# TUDSSL_condenar__Hardware_PCBs_Logger_Sc.net
KiCad netlist of a schematic drawn in Altium Designer
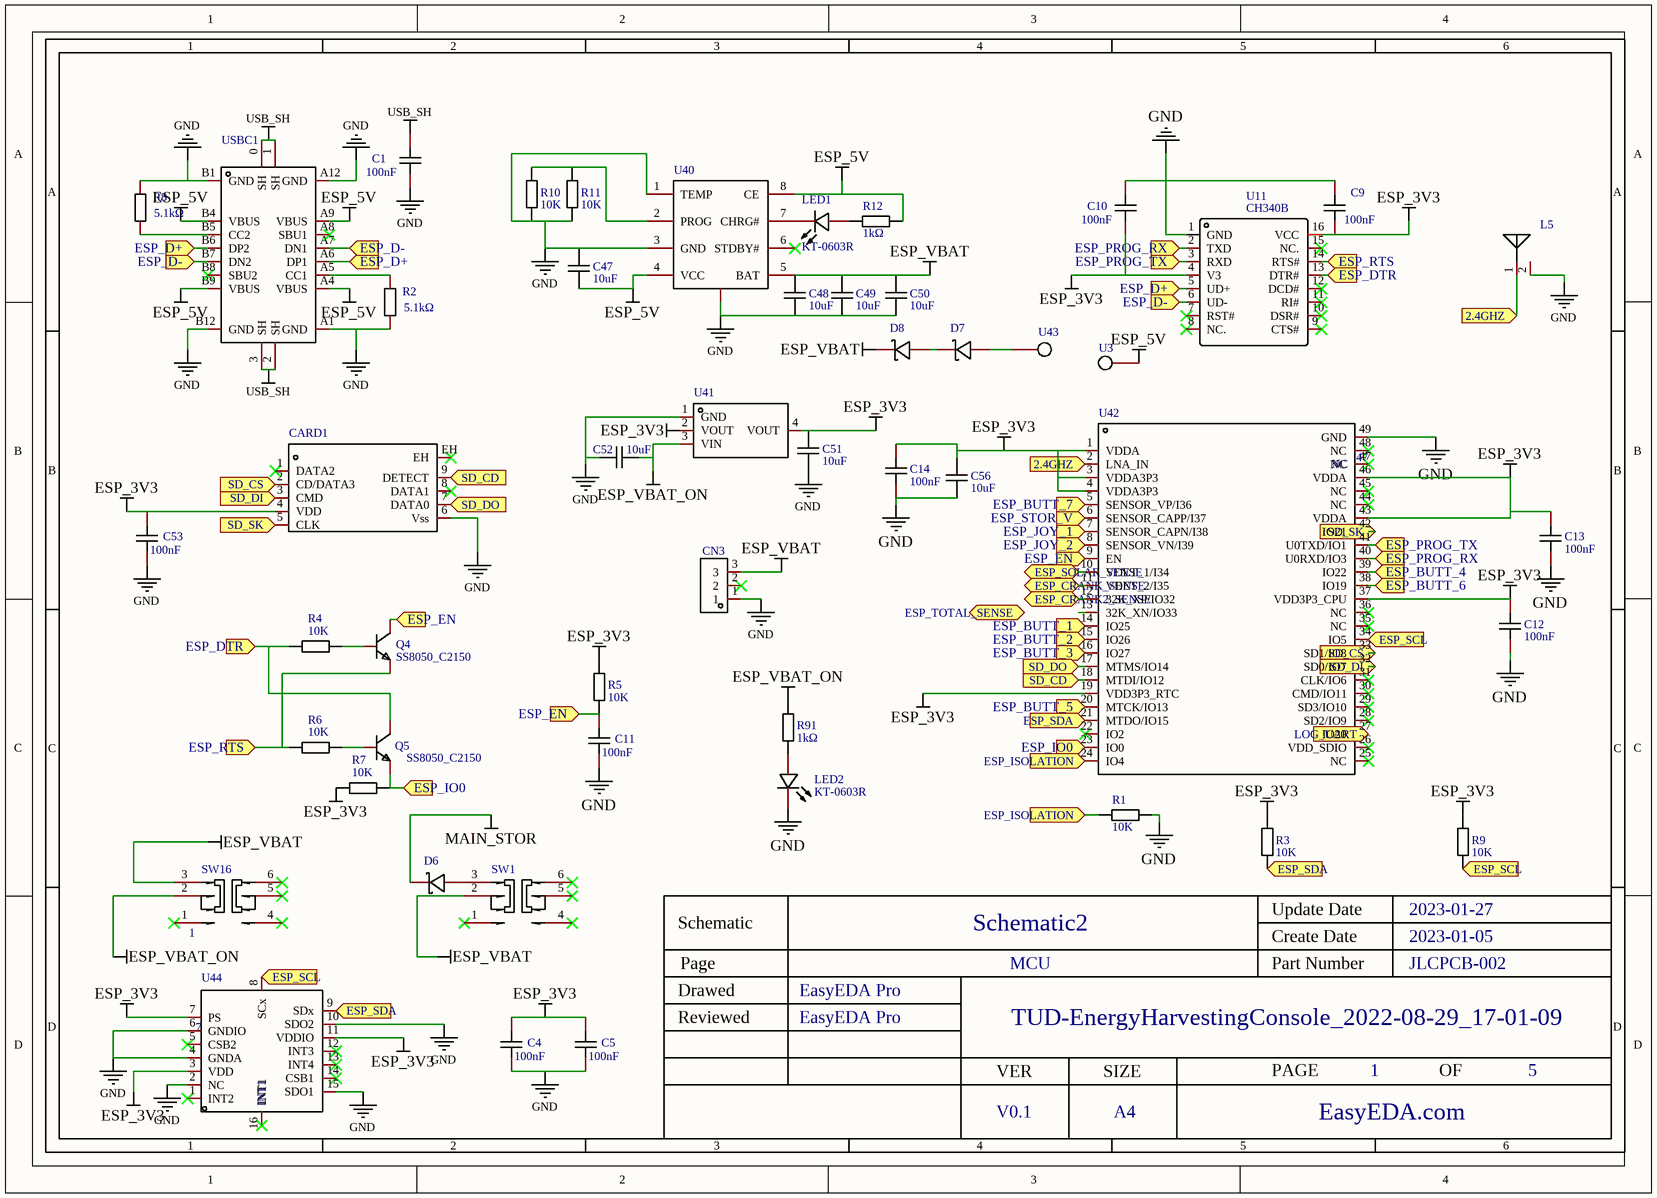
[diagram p0: TUDSSL_condenar__Hardware_PCBs_Logger_Schematic2__3_MCU.schdoc]

(export (version "E")
  (design (tool "Eeschema 10.0.6"))
  (components
    (comp (ref "C1")
      (value "100nF")
      (fields
        (field (name "NAME") "100nF")
        (field (name "MANUFACTURER") "YAGEO")
        (field (name "MANUFACTURER PART") "CC0603KRX7R9BB104")
      )
      (libsource (lib "altium-import") (part "root_1_CC0603KRX7R9BB104_"))
    )
    (comp (ref "C4")
      (value "100nF")
      (fields
        (field (name "NAME") "100nF")
        (field (name "MANUFACTURER") "YAGEO")
        (field (name "MANUFACTURER PART") "CC0603KRX7R9BB104")
      )
      (libsource (lib "altium-import") (part "root_1_CC0603KRX7R9BB104_"))
    )
    (comp (ref "C5")
      (value "100nF")
      (fields
        (field (name "NAME") "100nF")
        (field (name "MANUFACTURER") "YAGEO")
        (field (name "MANUFACTURER PART") "CC0603KRX7R9BB104")
      )
      (libsource (lib "altium-import") (part "root_1_CC0603KRX7R9BB104_"))
    )
    (comp (ref "C9")
      (value "100nF")
      (fields
        (field (name "NAME") "100nF")
        (field (name "MANUFACTURER") "YAGEO")
        (field (name "MANUFACTURER PART") "CC0603KRX7R9BB104")
      )
      (libsource (lib "altium-import") (part "root_1_CC0603KRX7R9BB104_"))
    )
    (comp (ref "C10")
      (value "100nF")
      (fields
        (field (name "NAME") "100nF")
        (field (name "MANUFACTURER") "YAGEO")
        (field (name "MANUFACTURER PART") "CC0603KRX7R9BB104")
      )
      (libsource (lib "altium-import") (part "root_1_CC0603KRX7R9BB104_"))
    )
    (comp (ref "C11")
      (value "100nF")
      (fields
        (field (name "NAME") "100nF")
        (field (name "MANUFACTURER") "YAGEO")
        (field (name "MANUFACTURER PART") "CC0603KRX7R9BB104")
      )
      (libsource (lib "altium-import") (part "root_1_CC0603KRX7R9BB104_"))
    )
    (comp (ref "C12")
      (value "100nF")
      (fields
        (field (name "NAME") "100nF")
        (field (name "MANUFACTURER PART") "CL05B104KO5NNNC")
        (field (name "MANUFACTURER") "SAMSUNG")
      )
      (libsource (lib "altium-import") (part "root_1_CL05B104KO5NNNC_"))
    )
    (comp (ref "C13")
      (value "100nF")
      (fields
        (field (name "NAME") "100nF")
        (field (name "MANUFACTURER PART") "CL05B104KO5NNNC")
        (field (name "MANUFACTURER") "SAMSUNG")
      )
      (libsource (lib "altium-import") (part "root_1_CL05B104KO5NNNC_"))
    )
    (comp (ref "C14")
      (value "100nF")
      (fields
        (field (name "NAME") "100nF")
        (field (name "MANUFACTURER PART") "CL05B104KO5NNNC")
        (field (name "MANUFACTURER") "SAMSUNG")
      )
      (libsource (lib "altium-import") (part "root_1_CL05B104KO5NNNC_"))
    )
    (comp (ref "C47")
      (value "10uF")
      (fields
        (field (name "NAME") "10uF")
        (field (name "MANUFACTURER PART") "CL05A106MQ5NUNC")
        (field (name "MANUFACTURER") "SAMSUNG")
      )
      (libsource (lib "altium-import") (part "root_3_CL05A106MQ5NUNC_"))
    )
    (comp (ref "C48")
      (value "10uF")
      (fields
        (field (name "NAME") "10uF")
        (field (name "MANUFACTURER PART") "CL05A106MQ5NUNC")
        (field (name "MANUFACTURER") "SAMSUNG")
      )
      (libsource (lib "altium-import") (part "root_3_CL05A106MQ5NUNC_"))
    )
    (comp (ref "C49")
      (value "10uF")
      (fields
        (field (name "NAME") "10uF")
        (field (name "MANUFACTURER PART") "CL05A106MQ5NUNC")
        (field (name "MANUFACTURER") "SAMSUNG")
      )
      (libsource (lib "altium-import") (part "root_3_CL05A106MQ5NUNC_"))
    )
    (comp (ref "C50")
      (value "10uF")
      (fields
        (field (name "NAME") "10uF")
        (field (name "MANUFACTURER PART") "CL05A106MQ5NUNC")
        (field (name "MANUFACTURER") "SAMSUNG")
      )
      (libsource (lib "altium-import") (part "root_3_CL05A106MQ5NUNC_"))
    )
    (comp (ref "C51")
      (value "10uF")
      (fields
        (field (name "NAME") "10uF")
        (field (name "MANUFACTURER PART") "CL05A106MQ5NUNC")
        (field (name "MANUFACTURER") "SAMSUNG")
      )
      (libsource (lib "altium-import") (part "root_3_CL05A106MQ5NUNC_"))
    )
    (comp (ref "C52")
      (value "10uF")
      (fields
        (field (name "NAME") "10uF")
        (field (name "MANUFACTURER PART") "CL05A106MQ5NUNC")
        (field (name "MANUFACTURER") "SAMSUNG")
      )
      (libsource (lib "altium-import") (part "root_0_CL05A106MQ5NUNC_"))
    )
    (comp (ref "C53")
      (value "100nF")
      (fields
        (field (name "NAME") "100nF")
        (field (name "MANUFACTURER") "YAGEO")
        (field (name "MANUFACTURER PART") "CC0603KRX7R9BB104")
      )
      (libsource (lib "altium-import") (part "root_1_CC0603KRX7R9BB104_"))
    )
    (comp (ref "C56")
      (value "10uF")
      (fields
        (field (name "NAME") "10uF")
        (field (name "MANUFACTURER PART") "CL05A106MQ5NUNC")
        (field (name "MANUFACTURER") "SAMSUNG")
      )
      (libsource (lib "altium-import") (part "root_3_CL05A106MQ5NUNC_"))
    )
    (comp (ref "CARD1")
      (value "473521001")
      (fields (field (name "MANUFACTURER") "MOLEX"))
      (libsource (lib "altium-import") (part "root_0_473521001_"))
    )
    (comp (ref "CN3")
      (value "X1502WR-03K-N0SN")
      (fields (field (name "MANUFACTURER") "XKB Connectivity(中国星坤)"))
      (libsource (lib "altium-import") (part "root_2_X1502WR-03K-N0SN_"))
    )
    (comp (ref "D6")
      (value "SS54")
      (description "Reverse Voltage (Vr):40V Average Rectified Current (Io):5A Forward Voltage (Vf@If):550mV@5A")
      (fields (field (name "MANUFACTURER") "MDD"))
      (libsource (lib "altium-import") (part "root_0_SS54_"))
    )
    (comp (ref "D7")
      (value "SS54")
      (description "Reverse Voltage (Vr):40V Average Rectified Current (Io):5A Forward Voltage (Vf@If):550mV@5A")
      (fields (field (name "MANUFACTURER") "MDD"))
      (libsource (lib "altium-import") (part "root_0_SS54_"))
    )
    (comp (ref "D8")
      (value "SS54")
      (description "Reverse Voltage (Vr):40V Average Rectified Current (Io):5A Forward Voltage (Vf@If):550mV@5A")
      (fields (field (name "MANUFACTURER") "MDD"))
      (libsource (lib "altium-import") (part "root_0_SS54_"))
    )
    (comp (ref "L5")
      (value "SLDA92-2R660G-S1TF")
      (fields (field (name "MANUFACTURER") "Sunlord(顺络)"))
      (libsource (lib "altium-import") (part "root_0_SLDA92-2R660G-S1TF_"))
    )
    (comp (ref "LED1")
      (value "KT-0603R")
      (fields (field (name "NAME") "KT-0603R") (field (name "MANUFACTURER") "KENTO"))
      (libsource (lib "altium-import") (part "root_0_KT-0603R_"))
    )
    (comp (ref "LED2")
      (value "KT-0603R")
      (fields (field (name "NAME") "KT-0603R") (field (name "MANUFACTURER") "KENTO"))
      (libsource (lib "altium-import") (part "root_1_KT-0603R_"))
    )
    (comp (ref "Q4")
      (value "SS8050_C2150")
      (fields
        (field (name "NAME") "SS8050_C2150")
        (field (name "MANUFACTURER") "CJ")
        (field (name "MANUFACTURER PART") "SS8050")
      )
      (libsource (lib "altium-import") (part "root_0_SS8050_"))
    )
    (comp (ref "Q5")
      (value "SS8050_C2150")
      (fields
        (field (name "NAME") "SS8050_C2150")
        (field (name "MANUFACTURER") "CJ")
        (field (name "MANUFACTURER PART") "SS8050")
      )
      (libsource (lib "altium-import") (part "root_0_SS8050_"))
    )
    (comp (ref "R1")
      (value "10K")
      (fields
        (field (name "NAME") "10K")
        (field (name "MANUFACTURER") "UniOhm")
        (field (name "MANUFACTURER PART") "0603WAF1002T5E")
      )
      (libsource (lib "altium-import") (part "root_2_0603WAF1002T5E_"))
    )
    (comp (ref "R2")
      (value "5.1kΩ")
      (fields
        (field (name "MANUFACTURER") "UNI-ROYAL(厚声)")
        (field (name "MANUFACTURER PART") "0603WAF5101T5E")
        (field (name "TOLERANCE") "±1%")
      )
      (libsource (lib "altium-import") (part "root_1_0603WAF5101T5E_"))
    )
    (comp (ref "R3")
      (value "10K")
      (fields
        (field (name "NAME") "10K")
        (field (name "MANUFACTURER") "UniOhm")
        (field (name "MANUFACTURER PART") "0603WAF1002T5E")
      )
      (libsource (lib "altium-import") (part "root_1_0603WAF1002T5E_"))
    )
    (comp (ref "R4")
      (value "10K")
      (fields
        (field (name "NAME") "10K")
        (field (name "MANUFACTURER") "UniOhm")
        (field (name "MANUFACTURER PART") "0603WAF1002T5E")
      )
      (libsource (lib "altium-import") (part "root_0_0603WAF1002T5E_"))
    )
    (comp (ref "R5")
      (value "10K")
      (fields
        (field (name "NAME") "10K")
        (field (name "MANUFACTURER") "UniOhm")
        (field (name "MANUFACTURER PART") "0603WAF1002T5E")
      )
      (libsource (lib "altium-import") (part "root_1_0603WAF1002T5E_"))
    )
    (comp (ref "R6")
      (value "10K")
      (fields
        (field (name "NAME") "10K")
        (field (name "MANUFACTURER") "UniOhm")
        (field (name "MANUFACTURER PART") "0603WAF1002T5E")
      )
      (libsource (lib "altium-import") (part "root_0_0603WAF1002T5E_"))
    )
    (comp (ref "R7")
      (value "10K")
      (fields
        (field (name "NAME") "10K")
        (field (name "MANUFACTURER") "UniOhm")
        (field (name "MANUFACTURER PART") "0603WAF1002T5E")
      )
      (libsource (lib "altium-import") (part "root_2_0603WAF1002T5E_"))
    )
    (comp (ref "R8")
      (value "5.1kΩ")
      (fields
        (field (name "MANUFACTURER") "UNI-ROYAL(厚声)")
        (field (name "MANUFACTURER PART") "0603WAF5101T5E")
        (field (name "TOLERANCE") "±1%")
      )
      (libsource (lib "altium-import") (part "root_1_0603WAF5101T5E_"))
    )
    (comp (ref "R9")
      (value "10K")
      (fields
        (field (name "NAME") "10K")
        (field (name "MANUFACTURER") "UniOhm")
        (field (name "MANUFACTURER PART") "0603WAF1002T5E")
      )
      (libsource (lib "altium-import") (part "root_1_0603WAF1002T5E_"))
    )
    (comp (ref "R10")
      (value "10K")
      (fields
        (field (name "NAME") "10K")
        (field (name "MANUFACTURER") "UniOhm")
        (field (name "MANUFACTURER PART") "0603WAF1002T5E")
      )
      (libsource (lib "altium-import") (part "root_1_0603WAF1002T5E_"))
    )
    (comp (ref "R11")
      (value "10K")
      (fields
        (field (name "NAME") "10K")
        (field (name "MANUFACTURER") "UniOhm")
        (field (name "MANUFACTURER PART") "0603WAF1002T5E")
      )
      (libsource (lib "altium-import") (part "root_1_0603WAF1002T5E_"))
    )
    (comp (ref "R12")
      (value "1kΩ")
      (fields
        (field (name "NAME") "1kΩ")
        (field (name "MANUFACTURER") "UniOhm")
        (field (name "MANUFACTURER PART") "0603WAF1001T5E")
      )
      (libsource (lib "altium-import") (part "root_0_0603WAF1001T5E_"))
    )
    (comp (ref "R91")
      (value "1kΩ")
      (fields
        (field (name "NAME") "1kΩ")
        (field (name "MANUFACTURER") "UniOhm")
        (field (name "MANUFACTURER PART") "0603WAF1001T5E")
      )
      (libsource (lib "altium-import") (part "root_1_0603WAF1001T5E_"))
    )
    (comp (ref "SW1")
      (value "SS-3235S-L1")
      (fields (field (name "MANUFACTURER") "XKB Connectivity(中国星坤)"))
      (libsource (lib "altium-import") (part "root_1_SS-3235S-L1_"))
    )
    (comp (ref "SW16")
      (value "SS-3235S-L1")
      (fields (field (name "MANUFACTURER") "XKB Connectivity(中国星坤)") (field (name "NUMBER") "1"))
      (libsource (lib "altium-import") (part "root_1_SS-3235S-L1_"))
    )
    (comp (ref "U3") (value "SMD_PAD") (libsource (lib "altium-import") (part "root_2_SMD_PAD_")))
    (comp (ref "U11")
      (value "CH340B")
      (fields (field (name "NAME") "CH340B") (field (name "MANUFACTURER") "WCH"))
      (libsource (lib "altium-import") (part "root_0_CH340B_"))
    )
    (comp (ref "U40")
      (value "TP4056M")
      (fields (field (name "MANUFACTURER") "TOPPOWER(南京拓微)"))
      (libsource (lib "altium-import") (part "root_0_TP4056M_"))
    )
    (comp (ref "U41")
      (value "AMS1117-3.3")
      (fields (field (name "MANUFACTURER") "美国AMS"))
      (libsource (lib "altium-import") (part "root_0_AMS1117-3.3_"))
    )
    (comp (ref "U42")
      (value "ESP32-PICO-V3")
      (fields
        (field (name "MANUFACTURER") "ESPRESSIF(乐鑫)")
        (field (name "NAME") "NC")
        (field (name "NUMBER") "47")
      )
      (libsource (lib "altium-import") (part "root_0_ESP32-PICO-V3_"))
    )
    (comp (ref "U43") (value "SMD_PAD") (libsource (lib "altium-import") (part "root_0_SMD_PAD_")))
    (comp (ref "U44")
      (value "BMI055")
      (fields
        (field (name "MANUFACTURER") "Bosch(博世)")
        (field (name "NAME") "INT1")
        (field (name "NUMBER") "7")
      )
      (libsource (lib "altium-import") (part "root_1_BMI055_"))
    )
    (comp (ref "USBC1")
      (value "TYPE-C-31-M-12")
      (fields (field (name "MANUFACTURER") "韩国韩荣"))
      (libsource (lib "altium-import") (part "root_0_TYPE-C-31-M-12_"))
    )
  )
  (nets
    (net (code "1") (name "/2.4GHZ") (class "Default")
      (node (ref "L5") (pin "1") (pinfunction "1_1") (pintype "passive"))
      (node (ref "U42") (pin "2") (pinfunction "LNA_IN_2") (pintype "passive"))
    )
    (net (code "2") (name "/ESP_BUTT_1") (class "Default")
      (node (ref "U42") (pin "14") (pinfunction "IO25_14") (pintype "passive"))
    )
    (net (code "3") (name "/ESP_BUTT_2") (class "Default")
      (node (ref "U42") (pin "15") (pinfunction "IO26_15") (pintype "passive"))
    )
    (net (code "4") (name "/ESP_BUTT_3") (class "Default")
      (node (ref "U42") (pin "16") (pinfunction "IO27_16") (pintype "passive"))
    )
    (net (code "5") (name "/ESP_BUTT_4") (class "Default")
      (node (ref "U42") (pin "39") (pinfunction "IO22_39") (pintype "passive"))
    )
    (net (code "6") (name "/ESP_BUTT_5") (class "Default")
      (node (ref "U42") (pin "20") (pinfunction "MTCK/IO13_20") (pintype "passive"))
    )
    (net (code "7") (name "/ESP_BUTT_6") (class "Default")
      (node (ref "U42") (pin "38") (pinfunction "IO19_38") (pintype "passive"))
    )
    (net (code "8") (name "/ESP_BUTT_7") (class "Default")
      (node (ref "U42") (pin "5") (pinfunction "SENSOR_VP/I36_5") (pintype "passive"))
    )
    (net (code "9") (name "/ESP_CRANK2_SENSE") (class "Default")
      (node (ref "U42") (pin "12") (pinfunction "32K_XP/IO32_12") (pintype "passive"))
    )
    (net (code "10") (name "/ESP_CRANK_SENSE") (class "Default")
      (node (ref "U42") (pin "11") (pinfunction "VDET_2/I35_11") (pintype "passive"))
    )
    (net (code "11") (name "/ESP_D+") (class "Default")
      (node (ref "U11") (pin "5") (pinfunction "UD+_5") (pintype "passive"))
      (node (ref "USBC1") (pin "A6") (pinfunction "DP1_A6") (pintype "passive"))
      (node (ref "USBC1") (pin "B6") (pinfunction "DP2_B6") (pintype "passive"))
    )
    (net (code "12") (name "/ESP_D-") (class "Default")
      (node (ref "U11") (pin "6") (pinfunction "UD-_6") (pintype "passive"))
      (node (ref "USBC1") (pin "A7") (pinfunction "DN1_A7") (pintype "passive"))
      (node (ref "USBC1") (pin "B7") (pinfunction "DN2_B7") (pintype "passive"))
    )
    (net (code "13") (name "/ESP_DTR") (class "Default")
      (node (ref "Q5") (pin "3") (pinfunction "C_3") (pintype "passive"))
      (node (ref "R4") (pin "1") (pinfunction "1_1") (pintype "passive"))
      (node (ref "U11") (pin "13") (pinfunction "DTR#_13") (pintype "passive"))
    )
    (net (code "14") (name "/ESP_EN") (class "Default")
      (node (ref "C11") (pin "2") (pinfunction "2_2") (pintype "passive"))
      (node (ref "Q4") (pin "3") (pinfunction "C_3") (pintype "passive"))
      (node (ref "R5") (pin "1") (pinfunction "1_1") (pintype "passive"))
      (node (ref "U42") (pin "9") (pinfunction "EN_9") (pintype "passive"))
    )
    (net (code "15") (name "/ESP_IO0") (class "Default")
      (node (ref "Q5") (pin "2") (pinfunction "E_2") (pintype "passive"))
      (node (ref "R7") (pin "1") (pinfunction "1_1") (pintype "passive"))
      (node (ref "U42") (pin "23") (pinfunction "IO0_23") (pintype "passive"))
    )
    (net (code "16") (name "/ESP_ISOLATION") (class "Default")
      (node (ref "R1") (pin "2") (pinfunction "2_2") (pintype "passive"))
      (node (ref "U42") (pin "24") (pinfunction "IO4_24") (pintype "passive"))
    )
    (net (code "17") (name "/ESP_JOY_1") (class "Default")
      (node (ref "U42") (pin "7") (pinfunction "SENSOR_CAPN/I38_7") (pintype "passive"))
    )
    (net (code "18") (name "/ESP_JOY_2") (class "Default")
      (node (ref "U42") (pin "8") (pinfunction "SENSOR_VN/I39_8") (pintype "passive"))
    )
    (net (code "19") (name "/ESP_PROG_RX") (class "Default")
      (node (ref "U11") (pin "2") (pinfunction "TXD_2") (pintype "passive"))
      (node (ref "U42") (pin "40") (pinfunction "U0RXD/IO3_40") (pintype "passive"))
    )
    (net (code "20") (name "/ESP_PROG_TX") (class "Default")
      (node (ref "U11") (pin "3") (pinfunction "RXD_3") (pintype "passive"))
      (node (ref "U42") (pin "41") (pinfunction "U0TXD/IO1_41") (pintype "passive"))
    )
    (net (code "21") (name "/ESP_RTS") (class "Default")
      (node (ref "Q4") (pin "2") (pinfunction "E_2") (pintype "passive"))
      (node (ref "R6") (pin "1") (pinfunction "1_1") (pintype "passive"))
      (node (ref "U11") (pin "14") (pinfunction "RTS#_14") (pintype "passive"))
    )
    (net (code "22") (name "/ESP_SCL") (class "Default")
      (node (ref "R9") (pin "1") (pinfunction "1_1") (pintype "passive"))
      (node (ref "U42") (pin "34") (pinfunction "IO5_34") (pintype "passive"))
      (node (ref "U44") (pin "8") (pinfunction "SCx_8") (pintype "passive"))
    )
    (net (code "23") (name "/ESP_SDA") (class "Default")
      (node (ref "R3") (pin "1") (pinfunction "1_1") (pintype "passive"))
      (node (ref "U42") (pin "21") (pinfunction "MTDO/IO15_21") (pintype "passive"))
      (node (ref "U44") (pin "9") (pinfunction "SDx_9") (pintype "passive"))
    )
    (net (code "24") (name "/ESP_SOLAR_SENSE") (class "Default")
      (node (ref "U42") (pin "10") (pinfunction "VDET_1/I34_10") (pintype "passive"))
    )
    (net (code "25") (name "/ESP_STOR_V") (class "Default")
      (node (ref "U42") (pin "6") (pinfunction "SENSOR_CAPP/I37_6") (pintype "passive"))
    )
    (net (code "27") (name "/LOG_UART") (class "Default")
      (node (ref "U42") (pin "27") (pinfunction "IO20_27") (pintype "passive"))
    )
    (net (code "28") (name "/SD_CD") (class "Default")
      (node (ref "CARD1") (pin "9") (pinfunction "DETECT_9") (pintype "passive"))
      (node (ref "U42") (pin "18") (pinfunction "MTDI/IO12_18") (pintype "passive"))
    )
    (net (code "29") (name "/SD_CS") (class "Default")
      (node (ref "CARD1") (pin "2") (pinfunction "CD/DATA3_2") (pintype "passive"))
      (node (ref "U42") (pin "33") (pinfunction "SD1/IO8_33") (pintype "passive"))
    )
    (net (code "30") (name "/SD_DI") (class "Default")
      (node (ref "CARD1") (pin "3") (pinfunction "CMD_3") (pintype "passive"))
      (node (ref "U42") (pin "32") (pinfunction "SD0/IO7_32") (pintype "passive"))
    )
    (net (code "31") (name "/SD_DO") (class "Default")
      (node (ref "CARD1") (pin "7") (pinfunction "DATA0_7") (pintype "passive"))
      (node (ref "U42") (pin "17") (pinfunction "MTMS/IO14_17") (pintype "passive"))
    )
    (net (code "32") (name "/SD_SK") (class "Default")
      (node (ref "CARD1") (pin "5") (pinfunction "CLK_5") (pintype "passive"))
      (node (ref "U42") (pin "42") (pinfunction "IO21_42") (pintype "passive"))
    )
    (net (code "33") (name "ESP_3V3") (class "Default")
      (node (ref "C10") (pin "1") (pinfunction "1_1") (pintype "passive"))
      (node (ref "C12") (pin "2") (pinfunction "2_2") (pintype "passive"))
      (node (ref "C13") (pin "2") (pinfunction "2_2") (pintype "passive"))
      (node (ref "C14") (pin "2") (pinfunction "2_2") (pintype "passive"))
      (node (ref "C4") (pin "2") (pinfunction "2_2") (pintype "passive"))
      (node (ref "C5") (pin "2") (pinfunction "2_2") (pintype "passive"))
      (node (ref "C51") (pin "1") (pinfunction "1_1") (pintype "passive"))
      (node (ref "C53") (pin "2") (pinfunction "2_2") (pintype "passive"))
      (node (ref "C56") (pin "1") (pinfunction "1_1") (pintype "passive"))
      (node (ref "C9") (pin "1") (pinfunction "1_1") (pintype "passive"))
      (node (ref "CARD1") (pin "4") (pinfunction "VDD_4") (pintype "passive"))
      (node (ref "R3") (pin "2") (pinfunction "2_2") (pintype "passive"))
      (node (ref "R5") (pin "2") (pinfunction "2_2") (pintype "passive"))
      (node (ref "R7") (pin "2") (pinfunction "2_2") (pintype "passive"))
      (node (ref "R9") (pin "2") (pinfunction "2_2") (pintype "passive"))
      (node (ref "U11") (pin "16") (pinfunction "VCC_16") (pintype "passive"))
      (node (ref "U11") (pin "4") (pinfunction "V3_4") (pintype "passive"))
      (node (ref "U41") (pin "2") (pinfunction "VOUT_2") (pintype "passive"))
      (node (ref "U41") (pin "4") (pinfunction "VOUT_4") (pintype "passive"))
      (node (ref "U42") (pin "1") (pinfunction "VDDA_1") (pintype "passive"))
      (node (ref "U42") (pin "19") (pinfunction "VDD3P3_RTC_19") (pintype "passive"))
      (node (ref "U42") (pin "3") (pinfunction "VDDA3P3_3") (pintype "passive"))
      (node (ref "U42") (pin "37") (pinfunction "VDD3P3_CPU_37") (pintype "passive"))
      (node (ref "U42") (pin "4") (pinfunction "VDDA3P3_4") (pintype "passive"))
      (node (ref "U42") (pin "43") (pinfunction "VDDA_43") (pintype "passive"))
      (node (ref "U42") (pin "46") (pinfunction "VDDA_46") (pintype "passive"))
      (node (ref "U44") (pin "11") (pinfunction "VDDIO_11") (pintype "passive"))
      (node (ref "U44") (pin "3") (pinfunction "VDD_3") (pintype "passive"))
      (node (ref "U44") (pin "7") (pinfunction "PS_7") (pintype "passive"))
    )
    (net (code "34") (name "ESP_5V") (class "Default")
      (node (ref "C47") (pin "2") (pinfunction "2_2") (pintype "passive"))
      (node (ref "R12") (pin "2") (pinfunction "2_2") (pintype "passive"))
      (node (ref "U3") (pin "1") (pinfunction "1_1") (pintype "passive"))
      (node (ref "U40") (pin "4") (pinfunction "VCC_4") (pintype "passive"))
      (node (ref "U40") (pin "8") (pinfunction "CE_8") (pintype "passive"))
      (node (ref "USBC1") (pin "A4") (pinfunction "VBUS_A4") (pintype "passive"))
      (node (ref "USBC1") (pin "A9") (pinfunction "VBUS_A9") (pintype "passive"))
      (node (ref "USBC1") (pin "B4") (pinfunction "VBUS_B4") (pintype "passive"))
      (node (ref "USBC1") (pin "B9") (pinfunction "VBUS_B9") (pintype "passive"))
    )
    (net (code "35") (name "ESP_VBAT") (class "Default")
      (node (ref "C48") (pin "1") (pinfunction "1_1") (pintype "passive"))
      (node (ref "C49") (pin "1") (pinfunction "1_1") (pintype "passive"))
      (node (ref "C50") (pin "1") (pinfunction "1_1") (pintype "passive"))
      (node (ref "CN3") (pin "3") (pinfunction "3_3") (pintype "passive"))
      (node (ref "D8") (pin "2") (pinfunction "K_2") (pintype "passive"))
      (node (ref "SW1") (pin "2") (pinfunction "2_2") (pintype "passive"))
      (node (ref "SW16") (pin "3") (pinfunction "3_3") (pintype "passive"))
      (node (ref "U40") (pin "5") (pinfunction "BAT_5") (pintype "passive"))
    )
    (net (code "36") (name "ESP_VBAT_ON") (class "Default")
      (node (ref "C52") (pin "2") (pinfunction "2_2") (pintype "passive"))
      (node (ref "R91") (pin "2") (pinfunction "2_2") (pintype "passive"))
      (node (ref "SW16") (pin "2") (pinfunction "2_2") (pintype "passive"))
      (node (ref "U41") (pin "3") (pinfunction "VIN_3") (pintype "passive"))
    )
    (net (code "37") (name "GND") (class "Default")
      (node (ref "C1") (pin "1") (pinfunction "1_1") (pintype "passive"))
      (node (ref "C10") (pin "2") (pinfunction "2_2") (pintype "passive"))
      (node (ref "C11") (pin "1") (pinfunction "1_1") (pintype "passive"))
      (node (ref "C12") (pin "1") (pinfunction "1_1") (pintype "passive"))
      (node (ref "C13") (pin "1") (pinfunction "1_1") (pintype "passive"))
      (node (ref "C14") (pin "1") (pinfunction "1_1") (pintype "passive"))
      (node (ref "C4") (pin "1") (pinfunction "1_1") (pintype "passive"))
      (node (ref "C47") (pin "1") (pinfunction "1_1") (pintype "passive"))
      (node (ref "C48") (pin "2") (pinfunction "2_2") (pintype "passive"))
      (node (ref "C49") (pin "2") (pinfunction "2_2") (pintype "passive"))
      (node (ref "C5") (pin "1") (pinfunction "1_1") (pintype "passive"))
      (node (ref "C50") (pin "2") (pinfunction "2_2") (pintype "passive"))
      (node (ref "C51") (pin "2") (pinfunction "2_2") (pintype "passive"))
      (node (ref "C52") (pin "1") (pinfunction "1_1") (pintype "passive"))
      (node (ref "C53") (pin "1") (pinfunction "1_1") (pintype "passive"))
      (node (ref "C56") (pin "2") (pinfunction "2_2") (pintype "passive"))
      (node (ref "C9") (pin "2") (pinfunction "2_2") (pintype "passive"))
      (node (ref "CARD1") (pin "6") (pinfunction "Vss_6") (pintype "passive"))
      (node (ref "CN3") (pin "1") (pinfunction "1_1") (pintype "passive"))
      (node (ref "L5") (pin "2") (pinfunction "NC_2") (pintype "passive"))
      (node (ref "LED2") (pin "2") (pinfunction "K_2") (pintype "passive"))
      (node (ref "R1") (pin "1") (pinfunction "1_1") (pintype "passive"))
      (node (ref "R10") (pin "1") (pinfunction "1_1") (pintype "passive"))
      (node (ref "R11") (pin "1") (pinfunction "1_1") (pintype "passive"))
      (node (ref "R2") (pin "1") (pinfunction "1_1") (pintype "passive"))
      (node (ref "R8") (pin "2") (pinfunction "2_2") (pintype "passive"))
      (node (ref "U11") (pin "1") (pinfunction "GND_1") (pintype "passive"))
      (node (ref "U40") (pin "1") (pinfunction "TEMP_1") (pintype "passive"))
      (node (ref "U40") (pin "3") (pinfunction "GND_3") (pintype "passive"))
      (node (ref "U40") (pin "9") (pinfunction "9_9") (pintype "passive"))
      (node (ref "U41") (pin "1") (pinfunction "GND_1") (pintype "passive"))
      (node (ref "U42") (pin "49") (pinfunction "GND_49") (pintype "passive"))
      (node (ref "U44") (pin "10") (pinfunction "SDO2_10") (pintype "passive"))
      (node (ref "U44") (pin "15") (pinfunction "SDO1_15") (pintype "passive"))
      (node (ref "U44") (pin "2") (pinfunction "NC_2") (pintype "passive"))
      (node (ref "U44") (pin "4") (pinfunction "GNDA_4") (pintype "passive"))
      (node (ref "U44") (pin "6") (pinfunction "GNDIO_6") (pintype "passive"))
      (node (ref "USBC1") (pin "A1") (pinfunction "GND_A1") (pintype "passive"))
      (node (ref "USBC1") (pin "A12") (pinfunction "GND_A12") (pintype "passive"))
      (node (ref "USBC1") (pin "B1") (pinfunction "GND_B1") (pintype "passive"))
      (node (ref "USBC1") (pin "B12") (pinfunction "GND_B12") (pintype "passive"))
    )
    (net (code "38") (name "MAIN_STOR") (class "Default")
      (node (ref "D6") (pin "2") (pinfunction "K_2") (pintype "passive"))
    )
    (net (code "39") (name "Net-(D6-A)") (class "Default")
      (node (ref "D6") (pin "1") (pinfunction "A_1") (pintype "passive"))
      (node (ref "SW1") (pin "3") (pinfunction "3_3") (pintype "passive"))
    )
    (net (code "40") (name "Net-(D7-A)") (class "Default")
      (node (ref "D7") (pin "1") (pinfunction "A_1") (pintype "passive"))
      (node (ref "U43") (pin "1") (pinfunction "1_1") (pintype "passive"))
    )
    (net (code "41") (name "Net-(D7-K)") (class "Default")
      (node (ref "D7") (pin "2") (pinfunction "K_2") (pintype "passive"))
      (node (ref "D8") (pin "1") (pinfunction "A_1") (pintype "passive"))
    )
    (net (code "42") (name "Net-(LED1-A)") (class "Default")
      (node (ref "LED1") (pin "1") (pinfunction "A_1") (pintype "passive"))
      (node (ref "R12") (pin "1") (pinfunction "1_1") (pintype "passive"))
    )
    (net (code "43") (name "Net-(LED1-K)") (class "Default")
      (node (ref "LED1") (pin "2") (pinfunction "K_2") (pintype "passive"))
      (node (ref "U40") (pin "7") (pinfunction "CHRG#_7") (pintype "passive"))
    )
    (net (code "44") (name "Net-(LED2-A)") (class "Default")
      (node (ref "LED2") (pin "1") (pinfunction "A_1") (pintype "passive"))
      (node (ref "R91") (pin "1") (pinfunction "1_1") (pintype "passive"))
    )
    (net (code "45") (name "Net-(Q4-B)") (class "Default")
      (node (ref "Q4") (pin "1") (pinfunction "B_1") (pintype "passive"))
      (node (ref "R4") (pin "2") (pinfunction "2_2") (pintype "passive"))
    )
    (net (code "46") (name "Net-(Q5-B)") (class "Default")
      (node (ref "Q5") (pin "1") (pinfunction "B_1") (pintype "passive"))
      (node (ref "R6") (pin "2") (pinfunction "2_2") (pintype "passive"))
    )
    (net (code "47") (name "Net-(U40-PROG)") (class "Default")
      (node (ref "R10") (pin "2") (pinfunction "2_2") (pintype "passive"))
      (node (ref "R11") (pin "2") (pinfunction "2_2") (pintype "passive"))
      (node (ref "U40") (pin "2") (pinfunction "PROG_2") (pintype "passive"))
    )
    (net (code "48") (name "Net-(USBC1-CC1)") (class "Default")
      (node (ref "R2") (pin "2") (pinfunction "2_2") (pintype "passive"))
      (node (ref "USBC1") (pin "A5") (pinfunction "CC1_A5") (pintype "passive"))
    )
    (net (code "49") (name "Net-(USBC1-CC2)") (class "Default")
      (node (ref "R8") (pin "1") (pinfunction "1_1") (pintype "passive"))
      (node (ref "USBC1") (pin "B5") (pinfunction "CC2_B5") (pintype "passive"))
    )
    (net (code "50") (name "USB_SH") (class "Default")
      (node (ref "C1") (pin "2") (pinfunction "2_2") (pintype "passive"))
      (node (ref "USBC1") (pin "0") (pinfunction "SH_0") (pintype "passive"))
      (node (ref "USBC1") (pin "1") (pinfunction "SH_1") (pintype "passive"))
      (node (ref "USBC1") (pin "2") (pinfunction "SH_2") (pintype "passive"))
      (node (ref "USBC1") (pin "3") (pinfunction "SH_3") (pintype "passive"))
    )
    (net (code "51") (name "unconnected-(CARD1-DATA1-Pad8)") (class "Default")
      (node (ref "CARD1") (pin "8") (pinfunction "DATA1_8") (pintype "passive+no_connect"))
    )
    (net (code "52") (name "unconnected-(CARD1-DATA2-Pad1)") (class "Default")
      (node (ref "CARD1") (pin "1") (pinfunction "DATA2_1") (pintype "passive+no_connect"))
    )
    (net (code "53") (name "unconnected-(CARD1-PadEH)") (class "Default")
      (node (ref "CARD1") (pin "EH") (pinfunction "EH_EH") (pintype "passive+no_connect"))
    )
    (net (code "54") (name "unconnected-(CN3-Pad2)") (class "Default")
      (node (ref "CN3") (pin "2") (pinfunction "2_2") (pintype "passive+no_connect"))
    )
    (net (code "55") (name "unconnected-(SW1-Pad1)") (class "Default")
      (node (ref "SW1") (pin "1") (pinfunction "1_1") (pintype "passive+no_connect"))
    )
    (net (code "56") (name "unconnected-(SW1-Pad4)") (class "Default")
      (node (ref "SW1") (pin "4") (pinfunction "4_4") (pintype "passive+no_connect"))
    )
    (net (code "57") (name "unconnected-(SW1-Pad5)") (class "Default")
      (node (ref "SW1") (pin "5") (pinfunction "5_5") (pintype "passive+no_connect"))
    )
    (net (code "58") (name "unconnected-(SW1-Pad6)") (class "Default")
      (node (ref "SW1") (pin "6") (pinfunction "6_6") (pintype "passive+no_connect"))
    )
    (net (code "59") (name "unconnected-(SW16-Pad1)") (class "Default")
      (node (ref "SW16") (pin "1") (pinfunction "1_1") (pintype "passive+no_connect"))
    )
    (net (code "60") (name "unconnected-(SW16-Pad4)") (class "Default")
      (node (ref "SW16") (pin "4") (pinfunction "4_4") (pintype "passive+no_connect"))
    )
    (net (code "61") (name "unconnected-(SW16-Pad5)") (class "Default")
      (node (ref "SW16") (pin "5") (pinfunction "5_5") (pintype "passive+no_connect"))
    )
    (net (code "62") (name "unconnected-(SW16-Pad6)") (class "Default")
      (node (ref "SW16") (pin "6") (pinfunction "6_6") (pintype "passive+no_connect"))
    )
    (net (code "63") (name "unconnected-(U11-CTS#-Pad9)") (class "Default")
      (node (ref "U11") (pin "9") (pinfunction "CTS#_9") (pintype "passive+no_connect"))
    )
    (net (code "64") (name "unconnected-(U11-DCD#-Pad12)") (class "Default")
      (node (ref "U11") (pin "12") (pinfunction "DCD#_12") (pintype "passive+no_connect"))
    )
    (net (code "65") (name "unconnected-(U11-DSR#-Pad10)") (class "Default")
      (node (ref "U11") (pin "10") (pinfunction "DSR#_10") (pintype "passive+no_connect"))
    )
    (net (code "66") (name "unconnected-(U11-NC.-Pad8)") (class "Default")
      (node (ref "U11") (pin "8") (pinfunction "NC._8") (pintype "passive+no_connect"))
    )
    (net (code "67") (name "unconnected-(U11-NC.-Pad15)") (class "Default")
      (node (ref "U11") (pin "15") (pinfunction "NC._15") (pintype "passive+no_connect"))
    )
    (net (code "68") (name "unconnected-(U11-RI#-Pad11)") (class "Default")
      (node (ref "U11") (pin "11") (pinfunction "RI#_11") (pintype "passive+no_connect"))
    )
    (net (code "69") (name "unconnected-(U11-RST#-Pad7)") (class "Default")
      (node (ref "U11") (pin "7") (pinfunction "RST#_7") (pintype "passive+no_connect"))
    )
    (net (code "70") (name "unconnected-(U40-STDBY#-Pad6)") (class "Default")
      (node (ref "U40") (pin "6") (pinfunction "STDBY#_6") (pintype "passive+no_connect"))
    )
    (net (code "71") (name "unconnected-(U42-32K_XN{slash}IO33-Pad13)") (class "Default")
      (node (ref "U42") (pin "13") (pinfunction "32K_XN/IO33_13") (pintype "passive"))
    )
    (net (code "72") (name "unconnected-(U42-CLK{slash}IO6-Pad31)") (class "Default")
      (node (ref "U42") (pin "31") (pinfunction "CLK/IO6_31") (pintype "passive+no_connect"))
    )
    (net (code "73") (name "unconnected-(U42-CMD{slash}IO11-Pad30)") (class "Default")
      (node (ref "U42") (pin "30") (pinfunction "CMD/IO11_30") (pintype "passive+no_connect"))
    )
    (net (code "74") (name "unconnected-(U42-IO2-Pad22)") (class "Default")
      (node (ref "U42") (pin "22") (pinfunction "IO2_22") (pintype "passive+no_connect"))
    )
    (net (code "75") (name "unconnected-(U42-NC-Pad25)") (class "Default")
      (node (ref "U42") (pin "25") (pinfunction "NC_25") (pintype "passive+no_connect"))
    )
    (net (code "76") (name "unconnected-(U42-NC-Pad35)") (class "Default")
      (node (ref "U42") (pin "35") (pinfunction "NC_35") (pintype "passive+no_connect"))
    )
    (net (code "77") (name "unconnected-(U42-NC-Pad36)") (class "Default")
      (node (ref "U42") (pin "36") (pinfunction "NC_36") (pintype "passive+no_connect"))
    )
    (net (code "78") (name "unconnected-(U42-NC-Pad44)") (class "Default")
      (node (ref "U42") (pin "44") (pinfunction "NC_44") (pintype "passive+no_connect"))
    )
    (net (code "79") (name "unconnected-(U42-NC-Pad45)") (class "Default")
      (node (ref "U42") (pin "45") (pinfunction "NC_45") (pintype "passive+no_connect"))
    )
    (net (code "80") (name "unconnected-(U42-NC-Pad47)") (class "Default")
      (node (ref "U42") (pin "47") (pinfunction "NC_47") (pintype "passive+no_connect"))
    )
    (net (code "81") (name "unconnected-(U42-NC-Pad48)") (class "Default")
      (node (ref "U42") (pin "48") (pinfunction "NC_48") (pintype "passive+no_connect"))
    )
    (net (code "82") (name "unconnected-(U42-SD2{slash}IO9-Pad28)") (class "Default")
      (node (ref "U42") (pin "28") (pinfunction "SD2/IO9_28") (pintype "passive+no_connect"))
    )
    (net (code "83") (name "unconnected-(U42-SD3{slash}IO10-Pad29)") (class "Default")
      (node (ref "U42") (pin "29") (pinfunction "SD3/IO10_29") (pintype "passive+no_connect"))
    )
    (net (code "84") (name "unconnected-(U42-VDD_SDIO-Pad26)") (class "Default")
      (node (ref "U42") (pin "26") (pinfunction "VDD_SDIO_26") (pintype "passive+no_connect"))
    )
    (net (code "85") (name "unconnected-(U44-CSB1-Pad14)") (class "Default")
      (node (ref "U44") (pin "14") (pinfunction "CSB1_14") (pintype "passive+no_connect"))
    )
    (net (code "86") (name "unconnected-(U44-CSB2-Pad5)") (class "Default")
      (node (ref "U44") (pin "5") (pinfunction "CSB2_5") (pintype "passive+no_connect"))
    )
    (net (code "87") (name "unconnected-(U44-INT1-Pad16)") (class "Default")
      (node (ref "U44") (pin "16") (pinfunction "INT1_16") (pintype "passive+no_connect"))
    )
    (net (code "88") (name "unconnected-(U44-INT2-Pad1)") (class "Default")
      (node (ref "U44") (pin "1") (pinfunction "INT2_1") (pintype "passive+no_connect"))
    )
    (net (code "89") (name "unconnected-(U44-INT3-Pad12)") (class "Default")
      (node (ref "U44") (pin "12") (pinfunction "INT3_12") (pintype "passive+no_connect"))
    )
    (net (code "90") (name "unconnected-(U44-INT4-Pad13)") (class "Default")
      (node (ref "U44") (pin "13") (pinfunction "INT4_13") (pintype "passive+no_connect"))
    )
    (net (code "91") (name "unconnected-(USBC1-SBU1-PadA8)") (class "Default")
      (node (ref "USBC1") (pin "A8") (pinfunction "SBU1_A8") (pintype "passive+no_connect"))
    )
    (net (code "92") (name "unconnected-(USBC1-SBU2-PadB8)") (class "Default")
      (node (ref "USBC1") (pin "B8") (pinfunction "SBU2_B8") (pintype "passive+no_connect"))
    )
  )
)
